# ddrive-esp-deadrail-1-6-routed.net
KiCad netlist of a schematic drawn in EAGLE
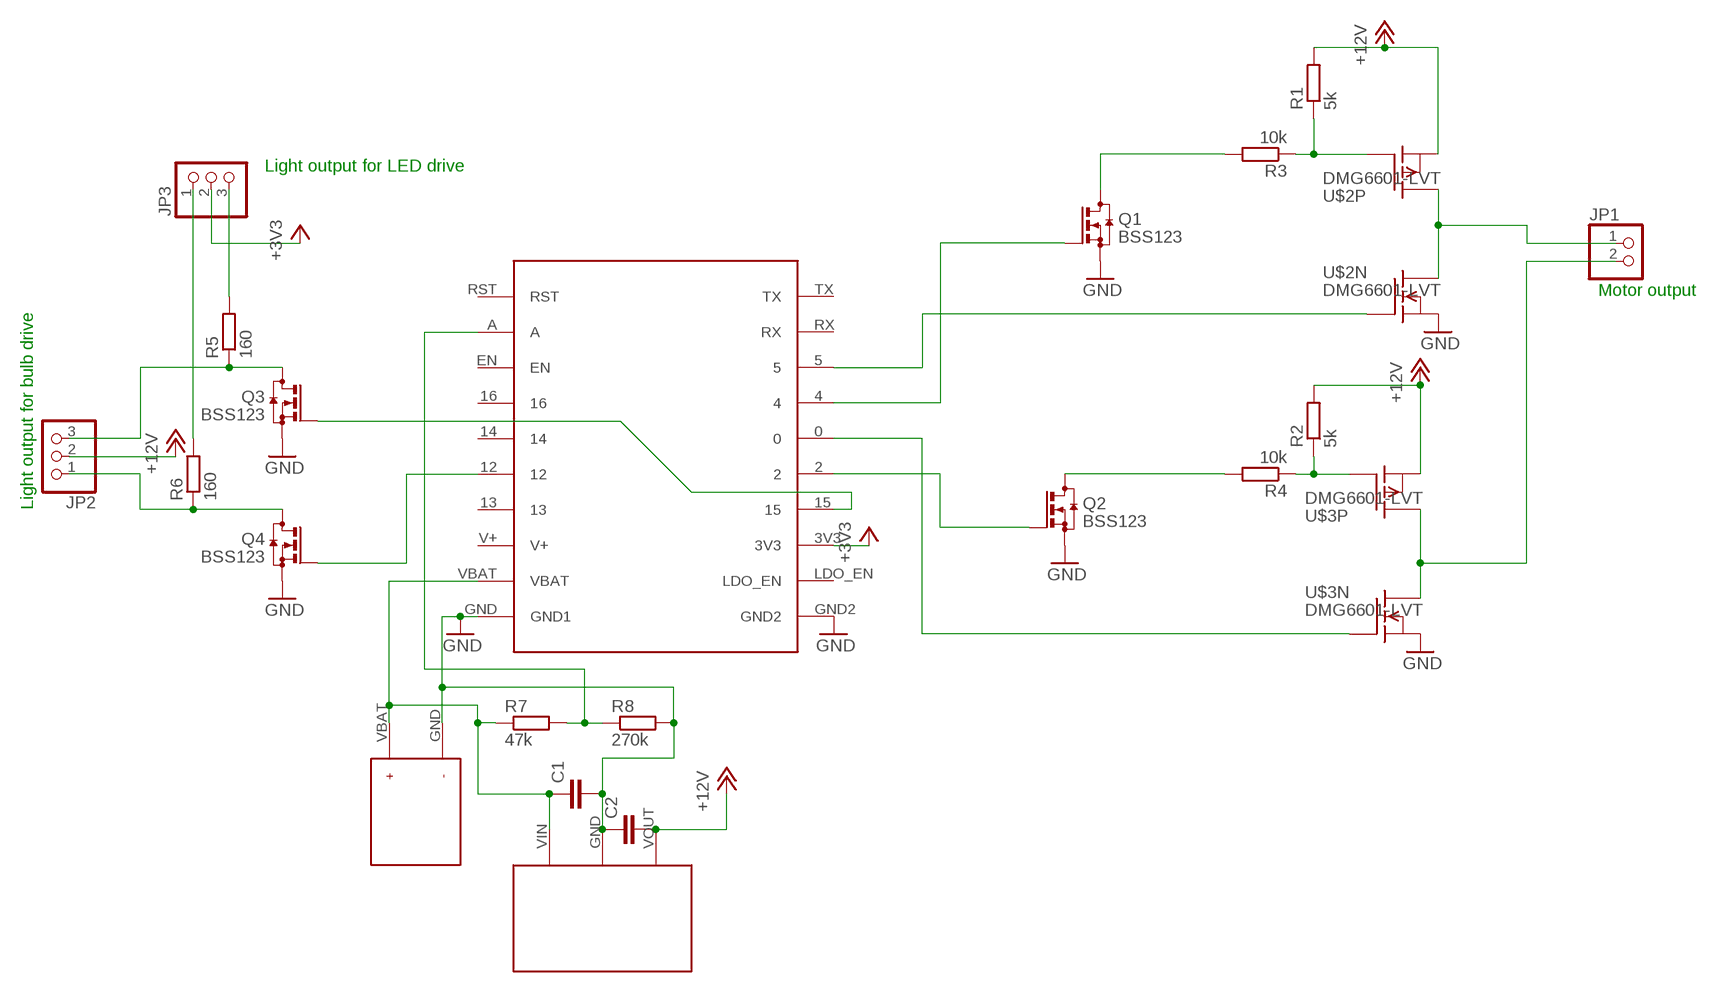
[diagram p0: schematic, sheet 1]

(export (version "E")
  (design (tool "Eeschema 10.0.6"))
  (components
    (comp (ref "C1")
      (value "C-EUC1210")
      (footprint "eagle-import:C1210")
      (libsource (lib "eagle-import") (part "C-EUC1210"))
    )
    (comp (ref "C2")
      (value "C-EUC1210")
      (footprint "eagle-import:C1210")
      (libsource (lib "eagle-import") (part "C-EUC1210"))
    )
    (comp (ref "JP1")
      (value "PINHD-1X2")
      (footprint "eagle-import:1X02")
      (libsource (lib "eagle-import") (part "PINHD-1X2"))
    )
    (comp (ref "JP2")
      (value "PINHD-1X3")
      (footprint "eagle-import:1X03")
      (libsource (lib "eagle-import") (part "PINHD-1X3"))
    )
    (comp (ref "JP3")
      (value "PINHD-1X3")
      (footprint "eagle-import:1X03")
      (libsource (lib "eagle-import") (part "PINHD-1X3"))
    )
    (comp (ref "Q1")
      (value "BSS123")
      (footprint "eagle-import:SOT23")
      (libsource (lib "eagle-import") (part "BSS123"))
    )
    (comp (ref "Q2")
      (value "BSS123")
      (footprint "eagle-import:SOT23")
      (libsource (lib "eagle-import") (part "BSS123"))
    )
    (comp (ref "Q3")
      (value "BSS123")
      (footprint "eagle-import:SOT23")
      (libsource (lib "eagle-import") (part "BSS123"))
    )
    (comp (ref "Q4")
      (value "BSS123")
      (footprint "eagle-import:SOT23")
      (libsource (lib "eagle-import") (part "BSS123"))
    )
    (comp (ref "R1")
      (value "5k")
      (footprint "eagle-import:R0805")
      (libsource (lib "eagle-import") (part "R-EU_R0805"))
    )
    (comp (ref "R2")
      (value "5k")
      (footprint "eagle-import:R0805")
      (libsource (lib "eagle-import") (part "R-EU_R0805"))
    )
    (comp (ref "R3")
      (value "10k")
      (footprint "eagle-import:R0805")
      (libsource (lib "eagle-import") (part "R-EU_R0805"))
    )
    (comp (ref "R4")
      (value "10k")
      (footprint "eagle-import:R0805")
      (libsource (lib "eagle-import") (part "R-EU_R0805"))
    )
    (comp (ref "R5")
      (value "160")
      (footprint "eagle-import:R0805")
      (libsource (lib "eagle-import") (part "R-EU_R0805"))
    )
    (comp (ref "R6")
      (value "160")
      (footprint "eagle-import:R0805")
      (libsource (lib "eagle-import") (part "R-EU_R0805"))
    )
    (comp (ref "R7")
      (value "47k")
      (footprint "eagle-import:R0805")
      (libsource (lib "eagle-import") (part "R-EU_R0805"))
    )
    (comp (ref "R8")
      (value "270k")
      (footprint "eagle-import:R0805")
      (libsource (lib "eagle-import") (part "R-EU_R0805"))
    )
    (comp (ref "U$1")
      (value "ESP12-HUZZAH")
      (footprint "eagle-import:ESP12-HUZZAH")
      (libsource (lib "eagle-import") (part "ESP12-HUZZAH"))
    )
    (comp (ref "U$2")
      (value "DMG6601-LVT")
      (footprint "eagle-import:TSOT-26")
      (libsource (lib "eagle-import") (part "DMG6601-LVT"))
    )
    (comp (ref "U$3")
      (value "DMG6601-LVT")
      (footprint "eagle-import:TSOT-26")
      (libsource (lib "eagle-import") (part "DMG6601-LVT"))
    )
    (comp (ref "U$4")
      (value "JST-PINHD")
      (footprint "eagle-import:JST-PINHDR")
      (libsource (lib "eagle-import") (part "JST-PINHD"))
    )
    (comp (ref "U$5")
      (value "POLOLU-VREG12")
      (footprint "eagle-import:POLOLU-REGULATOR")
      (libsource (lib "eagle-import") (part "POLOLU-VREG12"))
    )
  )
  (nets
    (net (code "1") (name "+3V3") (class "Default")
      (node (ref "JP3") (pin "2") (pinfunction "2_2") (pintype "passive"))
      (node (ref "U$1") (pin "3V3") (pinfunction "3V3_3V3") (pintype "power_in"))
    )
    (net (code "2") (name "+12V") (class "Default")
      (node (ref "C2") (pin "2") (pinfunction "2_2") (pintype "passive"))
      (node (ref "JP2") (pin "2") (pinfunction "2_2") (pintype "passive"))
      (node (ref "R1") (pin "2") (pinfunction "2_2") (pintype "passive"))
      (node (ref "R2") (pin "2") (pinfunction "2_2") (pintype "passive"))
      (node (ref "U$2") (pin "2") (pinfunction "S_2") (pintype "passive"))
      (node (ref "U$3") (pin "2") (pinfunction "S_2") (pintype "passive"))
      (node (ref "U$5") (pin "VOUT") (pinfunction "VOUT_VOUT") (pintype "bidirectional"))
    )
    (net (code "3") (name "/V+") (class "Default")
      (node (ref "U$1") (pin "V+") (pinfunction "V+_V+") (pintype "power_in"))
    )
    (net (code "4") (name "GND") (class "Default")
      (node (ref "C1") (pin "2") (pinfunction "2_2") (pintype "passive"))
      (node (ref "C2") (pin "1") (pinfunction "1_1") (pintype "passive"))
      (node (ref "Q1") (pin "2") (pinfunction "S_2") (pintype "passive"))
      (node (ref "Q2") (pin "2") (pinfunction "S_2") (pintype "passive"))
      (node (ref "Q3") (pin "2") (pinfunction "S_2") (pintype "passive"))
      (node (ref "Q4") (pin "2") (pinfunction "S_2") (pintype "passive"))
      (node (ref "R8") (pin "2") (pinfunction "2_2") (pintype "passive"))
      (node (ref "U$1") (pin "GND") (pinfunction "GND1_GND") (pintype "power_in"))
      (node (ref "U$1") (pin "GND2") (pinfunction "GND2_GND2") (pintype "power_in"))
      (node (ref "U$2") (pin "5") (pinfunction "S_5") (pintype "passive"))
      (node (ref "U$3") (pin "5") (pinfunction "S_5") (pintype "passive"))
      (node (ref "U$4") (pin "GND") (pinfunction "P$1_GND") (pintype "power_in"))
      (node (ref "U$5") (pin "GND") (pinfunction "GND_GND") (pintype "bidirectional"))
    )
    (net (code "5") (name "Net-(JP3-Pad1)") (class "Default")
      (node (ref "JP3") (pin "1") (pinfunction "1_1") (pintype "passive"))
      (node (ref "R6") (pin "2") (pinfunction "2_2") (pintype "passive"))
    )
    (net (code "6") (name "Net-(JP3-Pad3)") (class "Default")
      (node (ref "JP3") (pin "3") (pinfunction "3_3") (pintype "passive"))
      (node (ref "R5") (pin "2") (pinfunction "2_2") (pintype "passive"))
    )
    (net (code "7") (name "Net-(Q1-D)") (class "Default")
      (node (ref "Q1") (pin "3") (pinfunction "D_3") (pintype "passive"))
      (node (ref "R3") (pin "2") (pinfunction "2_2") (pintype "passive"))
    )
    (net (code "8") (name "Net-(Q1-G)") (class "Default")
      (node (ref "Q1") (pin "1") (pinfunction "G_1") (pintype "passive"))
      (node (ref "U$1") (pin "4") (pinfunction "4_4") (pintype "bidirectional"))
    )
    (net (code "9") (name "Net-(Q2-D)") (class "Default")
      (node (ref "Q2") (pin "3") (pinfunction "D_3") (pintype "passive"))
      (node (ref "R4") (pin "2") (pinfunction "2_2") (pintype "passive"))
    )
    (net (code "10") (name "Net-(Q2-G)") (class "Default")
      (node (ref "Q2") (pin "1") (pinfunction "G_1") (pintype "passive"))
      (node (ref "U$1") (pin "2") (pinfunction "2_2") (pintype "bidirectional"))
    )
    (net (code "11") (name "Net-(Q3-D)") (class "Default")
      (node (ref "JP2") (pin "3") (pinfunction "3_3") (pintype "passive"))
      (node (ref "Q3") (pin "3") (pinfunction "D_3") (pintype "passive"))
      (node (ref "R5") (pin "1") (pinfunction "1_1") (pintype "passive"))
    )
    (net (code "12") (name "Net-(Q3-G)") (class "Default")
      (node (ref "Q3") (pin "1") (pinfunction "G_1") (pintype "passive"))
      (node (ref "U$1") (pin "15") (pinfunction "15_15") (pintype "bidirectional"))
    )
    (net (code "13") (name "Net-(Q4-D)") (class "Default")
      (node (ref "JP2") (pin "1") (pinfunction "1_1") (pintype "passive"))
      (node (ref "Q4") (pin "3") (pinfunction "D_3") (pintype "passive"))
      (node (ref "R6") (pin "1") (pinfunction "1_1") (pintype "passive"))
    )
    (net (code "14") (name "Net-(Q4-G)") (class "Default")
      (node (ref "Q4") (pin "1") (pinfunction "G_1") (pintype "passive"))
      (node (ref "U$1") (pin "12") (pinfunction "12_12") (pintype "bidirectional"))
    )
    (net (code "15") (name "Net-(R7-Pad2)") (class "Default")
      (node (ref "R7") (pin "2") (pinfunction "2_2") (pintype "passive"))
      (node (ref "R8") (pin "1") (pinfunction "1_1") (pintype "passive"))
      (node (ref "U$1") (pin "A") (pinfunction "A_A") (pintype "bidirectional"))
    )
    (net (code "16") (name "Net-(U$2A-D)") (class "Default")
      (node (ref "JP1") (pin "1") (pinfunction "1_1") (pintype "passive"))
      (node (ref "U$2") (pin "4") (pinfunction "D_4") (pintype "passive"))
      (node (ref "U$2") (pin "6") (pinfunction "D_6") (pintype "passive"))
    )
    (net (code "17") (name "Net-(U$2A-G)") (class "Default")
      (node (ref "U$1") (pin "5") (pinfunction "5_5") (pintype "bidirectional"))
      (node (ref "U$2") (pin "1") (pinfunction "G_1") (pintype "passive"))
    )
    (net (code "18") (name "Net-(U$2B-G)") (class "Default")
      (node (ref "R1") (pin "1") (pinfunction "1_1") (pintype "passive"))
      (node (ref "R3") (pin "1") (pinfunction "1_1") (pintype "passive"))
      (node (ref "U$2") (pin "3") (pinfunction "G_3") (pintype "passive"))
    )
    (net (code "19") (name "Net-(U$3A-D)") (class "Default")
      (node (ref "JP1") (pin "2") (pinfunction "2_2") (pintype "passive"))
      (node (ref "U$3") (pin "4") (pinfunction "D_4") (pintype "passive"))
      (node (ref "U$3") (pin "6") (pinfunction "D_6") (pintype "passive"))
    )
    (net (code "20") (name "Net-(U$3A-G)") (class "Default")
      (node (ref "U$1") (pin "0") (pinfunction "0_0") (pintype "bidirectional"))
      (node (ref "U$3") (pin "1") (pinfunction "G_1") (pintype "passive"))
    )
    (net (code "21") (name "Net-(U$3B-G)") (class "Default")
      (node (ref "R2") (pin "1") (pinfunction "1_1") (pintype "passive"))
      (node (ref "R4") (pin "1") (pinfunction "1_1") (pintype "passive"))
      (node (ref "U$3") (pin "3") (pinfunction "G_3") (pintype "passive"))
    )
    (net (code "22") (name "Net-(U$4-P$2)") (class "Default")
      (node (ref "C1") (pin "1") (pinfunction "1_1") (pintype "passive"))
      (node (ref "R7") (pin "1") (pinfunction "1_1") (pintype "passive"))
      (node (ref "U$1") (pin "VBAT") (pinfunction "VBAT_VBAT") (pintype "power_in"))
      (node (ref "U$4") (pin "VBAT") (pinfunction "P$2_VBAT") (pintype "power_in"))
      (node (ref "U$5") (pin "VIN") (pinfunction "VIN_VIN") (pintype "bidirectional"))
    )
    (net (code "23") (name "unconnected-(U$1-Pad13)") (class "Default")
      (node (ref "U$1") (pin "13") (pinfunction "13_13") (pintype "bidirectional"))
    )
    (net (code "24") (name "unconnected-(U$1-Pad14)") (class "Default")
      (node (ref "U$1") (pin "14") (pinfunction "14_14") (pintype "bidirectional"))
    )
    (net (code "25") (name "unconnected-(U$1-Pad16)") (class "Default")
      (node (ref "U$1") (pin "16") (pinfunction "16_16") (pintype "bidirectional"))
    )
    (net (code "26") (name "unconnected-(U$1-PadEN)") (class "Default")
      (node (ref "U$1") (pin "EN") (pinfunction "EN_EN") (pintype "bidirectional"))
    )
    (net (code "27") (name "unconnected-(U$1-PadLDO_EN)") (class "Default")
      (node (ref "U$1") (pin "LDO_EN") (pinfunction "LDO_EN_LDO_EN") (pintype "bidirectional"))
    )
    (net (code "28") (name "unconnected-(U$1-PadRST)") (class "Default")
      (node (ref "U$1") (pin "RST") (pinfunction "RST_RST") (pintype "bidirectional"))
    )
    (net (code "29") (name "unconnected-(U$1-PadRX)") (class "Default")
      (node (ref "U$1") (pin "RX") (pinfunction "RX_RX") (pintype "bidirectional"))
    )
    (net (code "30") (name "unconnected-(U$1-PadTX)") (class "Default")
      (node (ref "U$1") (pin "TX") (pinfunction "TX_TX") (pintype "bidirectional"))
    )
  )
)
